# Garbage.net
KiCad netlist of a schematic drawn in EAGLE
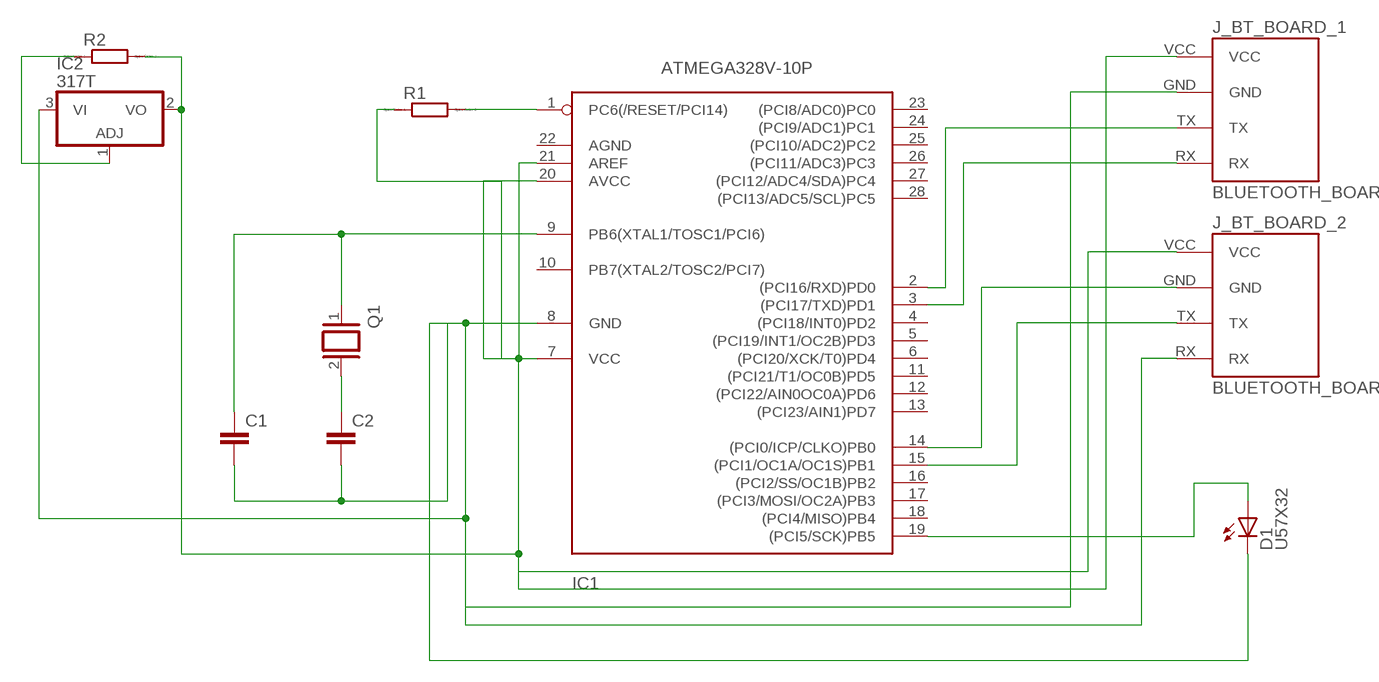
[diagram p0: schematic, sheet 1]

(export (version "E")
  (design (tool "Eeschema 10.0.6"))
  (components
    (comp (ref "C1")
      (value "C2,5-3")
      (footprint "eagle-import:C2.5-3")
      (libsource (lib "eagle-import") (part "C2,5-3"))
    )
    (comp (ref "C2")
      (value "C2,5-3")
      (footprint "eagle-import:C2.5-3")
      (libsource (lib "eagle-import") (part "C2,5-3"))
    )
    (comp (ref "D1")
      (value "U57X32")
      (footprint "eagle-import:U57X32")
      (libsource (lib "eagle-import") (part "U57X32"))
    )
    (comp (ref "IC1")
      (value "ATMEGA328V-10P")
      (footprint "eagle-import:DIL28-3")
      (libsource (lib "eagle-import") (part "ATMEGA328PV-10"))
    )
    (comp (ref "IC2")
      (value "317T")
      (footprint "eagle-import:TO220H")
      (libsource (lib "eagle-import") (part "317T"))
    )
    (comp (ref "J_BT_BOARD_1")
      (value "BLUETOOTH_BOARD")
      (footprint "eagle-import:BT_BOARD_FOOTPRINT")
      (libsource (lib "eagle-import") (part "BLUETOOTH_BOARD"))
    )
    (comp (ref "J_BT_BOARD_2")
      (value "BLUETOOTH_BOARD")
      (footprint "eagle-import:BT_BOARD_FOOTPRINT")
      (libsource (lib "eagle-import") (part "BLUETOOTH_BOARD"))
    )
    (comp (ref "Q1")
      (value "XTAL/S")
      (footprint "eagle-import:QS")
      (libsource (lib "eagle-import") (part "XTAL/S"))
    )
    (comp (ref "R1")
      (value "R0204/7")
      (footprint "eagle-import:0204_7")
      (libsource (lib "eagle-import") (part "R0204/7"))
    )
    (comp (ref "R2")
      (value "R0204/7")
      (footprint "eagle-import:0204_7")
      (libsource (lib "eagle-import") (part "R0204/7"))
    )
  )
  (nets
    (net (code "1") (name "Net-(C2-Pad1)") (class "Default")
      (node (ref "C2") (pin "1") (pinfunction "1_1") (pintype "passive"))
      (node (ref "Q1") (pin "2") (pinfunction "2_2") (pintype "passive"))
    )
    (net (code "2") (name "Net-(D1-C)") (class "Default")
      (node (ref "C1") (pin "2") (pinfunction "2_2") (pintype "passive"))
      (node (ref "C2") (pin "2") (pinfunction "2_2") (pintype "passive"))
      (node (ref "D1") (pin "K") (pinfunction "C_K") (pintype "passive"))
      (node (ref "IC1") (pin "8") (pinfunction "GND_8") (pintype "bidirectional"))
      (node (ref "IC2") (pin "3") (pinfunction "VI_3") (pintype "input"))
      (node (ref "J_BT_BOARD_1") (pin "GND") (pinfunction "GND_GND") (pintype "bidirectional"))
      (node (ref "J_BT_BOARD_2") (pin "RX") (pinfunction "RX_RX") (pintype "bidirectional"))
    )
    (net (code "3") (name "Net-(IC1-(PCI0{slash}ICP{slash}CLKO)PB0)") (class "Default")
      (node (ref "IC1") (pin "14") (pinfunction "(PCI0/ICP/CLKO)PB0_14") (pintype "bidirectional"))
      (node (ref "J_BT_BOARD_2") (pin "GND") (pinfunction "GND_GND") (pintype "bidirectional"))
    )
    (net (code "4") (name "Net-(IC1-(PCI1{slash}OC1A{slash}OC1S)PB1)") (class "Default")
      (node (ref "IC1") (pin "15") (pinfunction "(PCI1/OC1A/OC1S)PB1_15") (pintype "bidirectional"))
      (node (ref "J_BT_BOARD_2") (pin "TX") (pinfunction "TX_TX") (pintype "bidirectional"))
    )
    (net (code "5") (name "Net-(IC1-(PCI5{slash}SCK)PB5)") (class "Default")
      (node (ref "D1") (pin "A") (pinfunction "A_A") (pintype "passive"))
      (node (ref "IC1") (pin "19") (pinfunction "(PCI5/SCK)PB5_19") (pintype "bidirectional"))
    )
    (net (code "6") (name "Net-(IC1-(PCI16{slash}RXD)PD0)") (class "Default")
      (node (ref "IC1") (pin "2") (pinfunction "(PCI16/RXD)PD0_2") (pintype "bidirectional"))
      (node (ref "J_BT_BOARD_1") (pin "TX") (pinfunction "TX_TX") (pintype "bidirectional"))
    )
    (net (code "7") (name "Net-(IC1-(PCI17{slash}TXD)PD1)") (class "Default")
      (node (ref "IC1") (pin "3") (pinfunction "(PCI17/TXD)PD1_3") (pintype "bidirectional"))
      (node (ref "J_BT_BOARD_1") (pin "RX") (pinfunction "RX_RX") (pintype "bidirectional"))
    )
    (net (code "8") (name "Net-(IC1-AREF)") (class "Default")
      (node (ref "IC1") (pin "20") (pinfunction "AVCC_20") (pintype "bidirectional"))
      (node (ref "IC1") (pin "21") (pinfunction "AREF_21") (pintype "bidirectional"))
      (node (ref "IC1") (pin "7") (pinfunction "VCC_7") (pintype "bidirectional"))
      (node (ref "IC2") (pin "2") (pinfunction "VO_2") (pintype "passive"))
      (node (ref "J_BT_BOARD_1") (pin "VCC") (pinfunction "VCC_VCC") (pintype "bidirectional"))
      (node (ref "J_BT_BOARD_2") (pin "VCC") (pinfunction "VCC_VCC") (pintype "bidirectional"))
      (node (ref "R1") (pin "1") (pinfunction "1_1") (pintype "passive"))
      (node (ref "R2") (pin "2") (pinfunction "2_2") (pintype "passive"))
    )
    (net (code "9") (name "Net-(IC1-PB6(XTAL1{slash}TOSC1{slash}PCI6))") (class "Default")
      (node (ref "C1") (pin "1") (pinfunction "1_1") (pintype "passive"))
      (node (ref "IC1") (pin "9") (pinfunction "PB6(XTAL1/TOSC1/PCI6)_9") (pintype "bidirectional"))
      (node (ref "Q1") (pin "1") (pinfunction "1_1") (pintype "passive"))
    )
    (net (code "10") (name "Net-(IC1-PC6({slash}RESET{slash}PCI14))") (class "Default")
      (node (ref "IC1") (pin "1") (pinfunction "PC6(/RESET/PCI14)_1") (pintype "bidirectional"))
      (node (ref "R1") (pin "2") (pinfunction "2_2") (pintype "passive"))
    )
    (net (code "11") (name "Net-(IC2-ADJ)") (class "Default")
      (node (ref "IC2") (pin "1") (pinfunction "ADJ_1") (pintype "input"))
      (node (ref "R2") (pin "1") (pinfunction "1_1") (pintype "passive"))
    )
    (net (code "12") (name "unconnected-(IC1-(PCI2{slash}SS{slash}OC1B)PB2-Pad16)") (class "Default")
      (node (ref "IC1") (pin "16") (pinfunction "(PCI2/SS/OC1B)PB2_16") (pintype "bidirectional"))
    )
    (net (code "13") (name "unconnected-(IC1-(PCI3{slash}MOSI{slash}OC2A)PB3-Pad17)") (class "Default")
      (node (ref "IC1") (pin "17") (pinfunction "(PCI3/MOSI/OC2A)PB3_17") (pintype "bidirectional"))
    )
    (net (code "14") (name "unconnected-(IC1-(PCI4{slash}MISO)PB4-Pad18)") (class "Default")
      (node (ref "IC1") (pin "18") (pinfunction "(PCI4/MISO)PB4_18") (pintype "bidirectional"))
    )
    (net (code "15") (name "unconnected-(IC1-(PCI8{slash}ADC0)PC0-Pad23)") (class "Default")
      (node (ref "IC1") (pin "23") (pinfunction "(PCI8/ADC0)PC0_23") (pintype "bidirectional"))
    )
    (net (code "16") (name "unconnected-(IC1-(PCI9{slash}ADC1)PC1-Pad24)") (class "Default")
      (node (ref "IC1") (pin "24") (pinfunction "(PCI9/ADC1)PC1_24") (pintype "bidirectional"))
    )
    (net (code "17") (name "unconnected-(IC1-(PCI10{slash}ADC2)PC2-Pad25)") (class "Default")
      (node (ref "IC1") (pin "25") (pinfunction "(PCI10/ADC2)PC2_25") (pintype "bidirectional"))
    )
    (net (code "18") (name "unconnected-(IC1-(PCI11{slash}ADC3)PC3-Pad26)") (class "Default")
      (node (ref "IC1") (pin "26") (pinfunction "(PCI11/ADC3)PC3_26") (pintype "bidirectional"))
    )
    (net (code "19") (name "unconnected-(IC1-(PCI12{slash}ADC4{slash}SDA)PC4-Pad27)") (class "Default")
      (node (ref "IC1") (pin "27") (pinfunction "(PCI12/ADC4/SDA)PC4_27") (pintype "bidirectional"))
    )
    (net (code "20") (name "unconnected-(IC1-(PCI13{slash}ADC5{slash}SCL)PC5-Pad28)") (class "Default")
      (node (ref "IC1") (pin "28") (pinfunction "(PCI13/ADC5/SCL)PC5_28") (pintype "bidirectional"))
    )
    (net (code "21") (name "unconnected-(IC1-(PCI18{slash}INT0)PD2-Pad4)") (class "Default")
      (node (ref "IC1") (pin "4") (pinfunction "(PCI18/INT0)PD2_4") (pintype "bidirectional"))
    )
    (net (code "22") (name "unconnected-(IC1-(PCI19{slash}INT1{slash}OC2B)PD3-Pad5)") (class "Default")
      (node (ref "IC1") (pin "5") (pinfunction "(PCI19/INT1/OC2B)PD3_5") (pintype "bidirectional"))
    )
    (net (code "23") (name "unconnected-(IC1-(PCI20{slash}XCK{slash}T0)PD4-Pad6)") (class "Default")
      (node (ref "IC1") (pin "6") (pinfunction "(PCI20/XCK/T0)PD4_6") (pintype "bidirectional"))
    )
    (net (code "24") (name "unconnected-(IC1-(PCI21{slash}T1{slash}OC0B)PD5-Pad11)") (class "Default")
      (node (ref "IC1") (pin "11") (pinfunction "(PCI21/T1/OC0B)PD5_11") (pintype "bidirectional"))
    )
    (net (code "25") (name "unconnected-(IC1-(PCI22{slash}AIN0OC0A)PD6-Pad12)") (class "Default")
      (node (ref "IC1") (pin "12") (pinfunction "(PCI22/AIN0OC0A)PD6_12") (pintype "bidirectional"))
    )
    (net (code "26") (name "unconnected-(IC1-(PCI23{slash}AIN1)PD7-Pad13)") (class "Default")
      (node (ref "IC1") (pin "13") (pinfunction "(PCI23/AIN1)PD7_13") (pintype "bidirectional"))
    )
    (net (code "27") (name "unconnected-(IC1-AGND-Pad22)") (class "Default")
      (node (ref "IC1") (pin "22") (pinfunction "AGND_22") (pintype "bidirectional"))
    )
    (net (code "28") (name "unconnected-(IC1-PB7(XTAL2{slash}TOSC2{slash}PCI7)-Pad10)") (class "Default")
      (node (ref "IC1") (pin "10") (pinfunction "PB7(XTAL2/TOSC2/PCI7)_10") (pintype "bidirectional"))
    )
  )
)
